# DSPCONN.net
KiCad netlist of a schematic drawn in Altium Designer
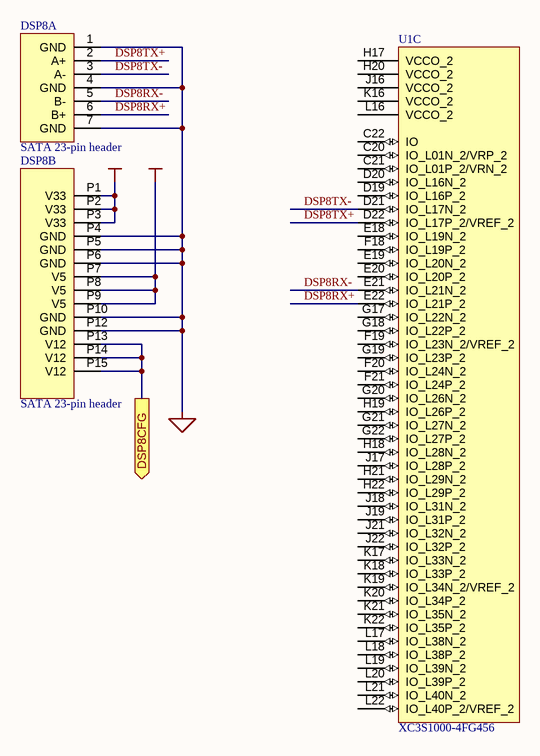
[diagram p0: DSPCONN.SCHDOC]

(export (version "E")
  (design (tool "Eeschema 10.0.6"))
  (components
    (comp (ref "DSP8")
      (value "SATA 23-pin header")
      (footprint "MOLEX 87713-1001")
      (libsource (lib "parts") (part "SATA-23"))
    )
    (comp (ref "U1")
      (value "XC3S1000-4FG456")
      (footprint "FG456")
      (description "Xilinx Spartan-3 FPGA")
      (libsource (lib "parts") (part "XC3S1000-4FG456"))
    )
  )
  (nets
    (net (code "1") (name "+5VCC") (class "Default")
      (node (ref "DSP8") (pin "P7") (pinfunction "V5_P7") (pintype "passive"))
      (node (ref "DSP8") (pin "P8") (pinfunction "V5_P8") (pintype "passive"))
      (node (ref "DSP8") (pin "P9") (pinfunction "V5_P9") (pintype "passive"))
    )
    (net (code "2") (name "/DSP8CFG") (class "Default")
      (node (ref "DSP8") (pin "P13") (pinfunction "V12_P13") (pintype "passive"))
      (node (ref "DSP8") (pin "P14") (pinfunction "V12_P14") (pintype "passive"))
      (node (ref "DSP8") (pin "P15") (pinfunction "V12_P15") (pintype "passive"))
    )
    (net (code "3") (name "/DSP8RX+") (class "Default")
      (node (ref "DSP8") (pin "6") (pinfunction "B+_6") (pintype "passive"))
      (node (ref "U1") (pin "E22") (pinfunction "IO_L21P_2_E22") (pintype "bidirectional"))
    )
    (net (code "4") (name "/DSP8RX-") (class "Default")
      (node (ref "DSP8") (pin "5") (pinfunction "B-_5") (pintype "passive"))
      (node (ref "U1") (pin "E21") (pinfunction "IO_L21N_2_E21") (pintype "bidirectional"))
    )
    (net (code "5") (name "/DSP8TX+") (class "Default")
      (node (ref "DSP8") (pin "2") (pinfunction "A+_2") (pintype "passive"))
      (node (ref "U1") (pin "D22") (pinfunction "IO_L17P_2/VREF_2_D22") (pintype "bidirectional"))
    )
    (net (code "6") (name "/DSP8TX-") (class "Default")
      (node (ref "DSP8") (pin "3") (pinfunction "A-_3") (pintype "passive"))
      (node (ref "U1") (pin "D21") (pinfunction "IO_L17N_2_D21") (pintype "bidirectional"))
    )
    (net (code "7") (name "GND") (class "Default")
      (node (ref "DSP8") (pin "1") (pinfunction "GND_1") (pintype "passive"))
      (node (ref "DSP8") (pin "4") (pinfunction "GND_4") (pintype "passive"))
      (node (ref "DSP8") (pin "7") (pinfunction "GND_7") (pintype "passive"))
      (node (ref "DSP8") (pin "P10") (pinfunction "GND_P10") (pintype "passive"))
      (node (ref "DSP8") (pin "P12") (pinfunction "GND_P12") (pintype "passive"))
      (node (ref "DSP8") (pin "P4") (pinfunction "GND_P4") (pintype "passive"))
      (node (ref "DSP8") (pin "P5") (pinfunction "GND_P5") (pintype "passive"))
      (node (ref "DSP8") (pin "P6") (pinfunction "GND_P6") (pintype "passive"))
    )
    (net (code "8") (name "VCC") (class "Default")
      (node (ref "DSP8") (pin "P1") (pinfunction "V33_P1") (pintype "passive"))
      (node (ref "DSP8") (pin "P2") (pinfunction "V33_P2") (pintype "passive"))
      (node (ref "DSP8") (pin "P3") (pinfunction "V33_P3") (pintype "passive"))
    )
    (net (code "9") (name "unconnected-(U1C-IO-PadC22)") (class "Default")
      (node (ref "U1") (pin "C22") (pinfunction "IO_C22") (pintype "bidirectional"))
    )
    (net (code "10") (name "unconnected-(U1C-IO_L01N_2{slash}VRP_2-PadC20)") (class "Default")
      (node (ref "U1") (pin "C20") (pinfunction "IO_L01N_2/VRP_2_C20") (pintype "bidirectional"))
    )
    (net (code "11") (name "unconnected-(U1C-IO_L01P_2{slash}VRN_2-PadC21)") (class "Default")
      (node (ref "U1") (pin "C21") (pinfunction "IO_L01P_2/VRN_2_C21") (pintype "bidirectional"))
    )
    (net (code "12") (name "unconnected-(U1C-IO_L16N_2-PadD20)") (class "Default")
      (node (ref "U1") (pin "D20") (pinfunction "IO_L16N_2_D20") (pintype "bidirectional"))
    )
    (net (code "13") (name "unconnected-(U1C-IO_L16P_2-PadD19)") (class "Default")
      (node (ref "U1") (pin "D19") (pinfunction "IO_L16P_2_D19") (pintype "bidirectional"))
    )
    (net (code "14") (name "unconnected-(U1C-IO_L19N_2-PadE18)") (class "Default")
      (node (ref "U1") (pin "E18") (pinfunction "IO_L19N_2_E18") (pintype "bidirectional"))
    )
    (net (code "15") (name "unconnected-(U1C-IO_L19P_2-PadF18)") (class "Default")
      (node (ref "U1") (pin "F18") (pinfunction "IO_L19P_2_F18") (pintype "bidirectional"))
    )
    (net (code "16") (name "unconnected-(U1C-IO_L20N_2-PadE19)") (class "Default")
      (node (ref "U1") (pin "E19") (pinfunction "IO_L20N_2_E19") (pintype "bidirectional"))
    )
    (net (code "17") (name "unconnected-(U1C-IO_L20P_2-PadE20)") (class "Default")
      (node (ref "U1") (pin "E20") (pinfunction "IO_L20P_2_E20") (pintype "bidirectional"))
    )
    (net (code "18") (name "unconnected-(U1C-IO_L22N_2-PadG17)") (class "Default")
      (node (ref "U1") (pin "G17") (pinfunction "IO_L22N_2_G17") (pintype "bidirectional"))
    )
    (net (code "19") (name "unconnected-(U1C-IO_L22P_2-PadG18)") (class "Default")
      (node (ref "U1") (pin "G18") (pinfunction "IO_L22P_2_G18") (pintype "bidirectional"))
    )
    (net (code "20") (name "unconnected-(U1C-IO_L23N_2{slash}VREF_2-PadF19)") (class "Default")
      (node (ref "U1") (pin "F19") (pinfunction "IO_L23N_2/VREF_2_F19") (pintype "bidirectional"))
    )
    (net (code "21") (name "unconnected-(U1C-IO_L23P_2-PadG19)") (class "Default")
      (node (ref "U1") (pin "G19") (pinfunction "IO_L23P_2_G19") (pintype "bidirectional"))
    )
    (net (code "22") (name "unconnected-(U1C-IO_L24N_2-PadF20)") (class "Default")
      (node (ref "U1") (pin "F20") (pinfunction "IO_L24N_2_F20") (pintype "bidirectional"))
    )
    (net (code "23") (name "unconnected-(U1C-IO_L24P_2-PadF21)") (class "Default")
      (node (ref "U1") (pin "F21") (pinfunction "IO_L24P_2_F21") (pintype "bidirectional"))
    )
    (net (code "24") (name "unconnected-(U1C-IO_L26N_2-PadG20)") (class "Default")
      (node (ref "U1") (pin "G20") (pinfunction "IO_L26N_2_G20") (pintype "bidirectional"))
    )
    (net (code "25") (name "unconnected-(U1C-IO_L26P_2-PadH19)") (class "Default")
      (node (ref "U1") (pin "H19") (pinfunction "IO_L26P_2_H19") (pintype "bidirectional"))
    )
    (net (code "26") (name "unconnected-(U1C-IO_L27N_2-PadG21)") (class "Default")
      (node (ref "U1") (pin "G21") (pinfunction "IO_L27N_2_G21") (pintype "bidirectional"))
    )
    (net (code "27") (name "unconnected-(U1C-IO_L27P_2-PadG22)") (class "Default")
      (node (ref "U1") (pin "G22") (pinfunction "IO_L27P_2_G22") (pintype "bidirectional"))
    )
    (net (code "28") (name "unconnected-(U1C-IO_L28N_2-PadH18)") (class "Default")
      (node (ref "U1") (pin "H18") (pinfunction "IO_L28N_2_H18") (pintype "bidirectional"))
    )
    (net (code "29") (name "unconnected-(U1C-IO_L28P_2-PadJ17)") (class "Default")
      (node (ref "U1") (pin "J17") (pinfunction "IO_L28P_2_J17") (pintype "bidirectional"))
    )
    (net (code "30") (name "unconnected-(U1C-IO_L29N_2-PadH21)") (class "Default")
      (node (ref "U1") (pin "H21") (pinfunction "IO_L29N_2_H21") (pintype "bidirectional"))
    )
    (net (code "31") (name "unconnected-(U1C-IO_L29P_2-PadH22)") (class "Default")
      (node (ref "U1") (pin "H22") (pinfunction "IO_L29P_2_H22") (pintype "bidirectional"))
    )
    (net (code "32") (name "unconnected-(U1C-IO_L31N_2-PadJ18)") (class "Default")
      (node (ref "U1") (pin "J18") (pinfunction "IO_L31N_2_J18") (pintype "bidirectional"))
    )
    (net (code "33") (name "unconnected-(U1C-IO_L31P_2-PadJ19)") (class "Default")
      (node (ref "U1") (pin "J19") (pinfunction "IO_L31P_2_J19") (pintype "bidirectional"))
    )
    (net (code "34") (name "unconnected-(U1C-IO_L32N_2-PadJ21)") (class "Default")
      (node (ref "U1") (pin "J21") (pinfunction "IO_L32N_2_J21") (pintype "bidirectional"))
    )
    (net (code "35") (name "unconnected-(U1C-IO_L32P_2-PadJ22)") (class "Default")
      (node (ref "U1") (pin "J22") (pinfunction "IO_L32P_2_J22") (pintype "bidirectional"))
    )
    (net (code "36") (name "unconnected-(U1C-IO_L33N_2-PadK17)") (class "Default")
      (node (ref "U1") (pin "K17") (pinfunction "IO_L33N_2_K17") (pintype "bidirectional"))
    )
    (net (code "37") (name "unconnected-(U1C-IO_L33P_2-PadK18)") (class "Default")
      (node (ref "U1") (pin "K18") (pinfunction "IO_L33P_2_K18") (pintype "bidirectional"))
    )
    (net (code "38") (name "unconnected-(U1C-IO_L34N_2{slash}VREF_2-PadK19)") (class "Default")
      (node (ref "U1") (pin "K19") (pinfunction "IO_L34N_2/VREF_2_K19") (pintype "bidirectional"))
    )
    (net (code "39") (name "unconnected-(U1C-IO_L34P_2-PadK20)") (class "Default")
      (node (ref "U1") (pin "K20") (pinfunction "IO_L34P_2_K20") (pintype "bidirectional"))
    )
    (net (code "40") (name "unconnected-(U1C-IO_L35N_2-PadK21)") (class "Default")
      (node (ref "U1") (pin "K21") (pinfunction "IO_L35N_2_K21") (pintype "bidirectional"))
    )
    (net (code "41") (name "unconnected-(U1C-IO_L35P_2-PadK22)") (class "Default")
      (node (ref "U1") (pin "K22") (pinfunction "IO_L35P_2_K22") (pintype "bidirectional"))
    )
    (net (code "42") (name "unconnected-(U1C-IO_L38N_2-PadL17)") (class "Default")
      (node (ref "U1") (pin "L17") (pinfunction "IO_L38N_2_L17") (pintype "bidirectional"))
    )
    (net (code "43") (name "unconnected-(U1C-IO_L38P_2-PadL18)") (class "Default")
      (node (ref "U1") (pin "L18") (pinfunction "IO_L38P_2_L18") (pintype "bidirectional"))
    )
    (net (code "44") (name "unconnected-(U1C-IO_L39N_2-PadL19)") (class "Default")
      (node (ref "U1") (pin "L19") (pinfunction "IO_L39N_2_L19") (pintype "bidirectional"))
    )
    (net (code "45") (name "unconnected-(U1C-IO_L39P_2-PadL20)") (class "Default")
      (node (ref "U1") (pin "L20") (pinfunction "IO_L39P_2_L20") (pintype "bidirectional"))
    )
    (net (code "46") (name "unconnected-(U1C-IO_L40N_2-PadL21)") (class "Default")
      (node (ref "U1") (pin "L21") (pinfunction "IO_L40N_2_L21") (pintype "bidirectional"))
    )
    (net (code "47") (name "unconnected-(U1C-IO_L40P_2{slash}VREF_2-PadL22)") (class "Default")
      (node (ref "U1") (pin "L22") (pinfunction "IO_L40P_2/VREF_2_L22") (pintype "bidirectional"))
    )
    (net (code "48") (name "unconnected-(U1C-VCCO_2-PadH17)") (class "Default")
      (node (ref "U1") (pin "H17") (pinfunction "VCCO_2_H17") (pintype "power_in"))
    )
    (net (code "49") (name "unconnected-(U1C-VCCO_2-PadH20)") (class "Default")
      (node (ref "U1") (pin "H20") (pinfunction "VCCO_2_H20") (pintype "power_in"))
    )
    (net (code "50") (name "unconnected-(U1C-VCCO_2-PadJ16)") (class "Default")
      (node (ref "U1") (pin "J16") (pinfunction "VCCO_2_J16") (pintype "power_in"))
    )
    (net (code "51") (name "unconnected-(U1C-VCCO_2-PadK16)") (class "Default")
      (node (ref "U1") (pin "K16") (pinfunction "VCCO_2_K16") (pintype "power_in"))
    )
    (net (code "52") (name "unconnected-(U1C-VCCO_2-PadL16)") (class "Default")
      (node (ref "U1") (pin "L16") (pinfunction "VCCO_2_L16") (pintype "power_in"))
    )
  )
)
